# BitBeaconS.net
KiCad netlist of a schematic drawn in EAGLE
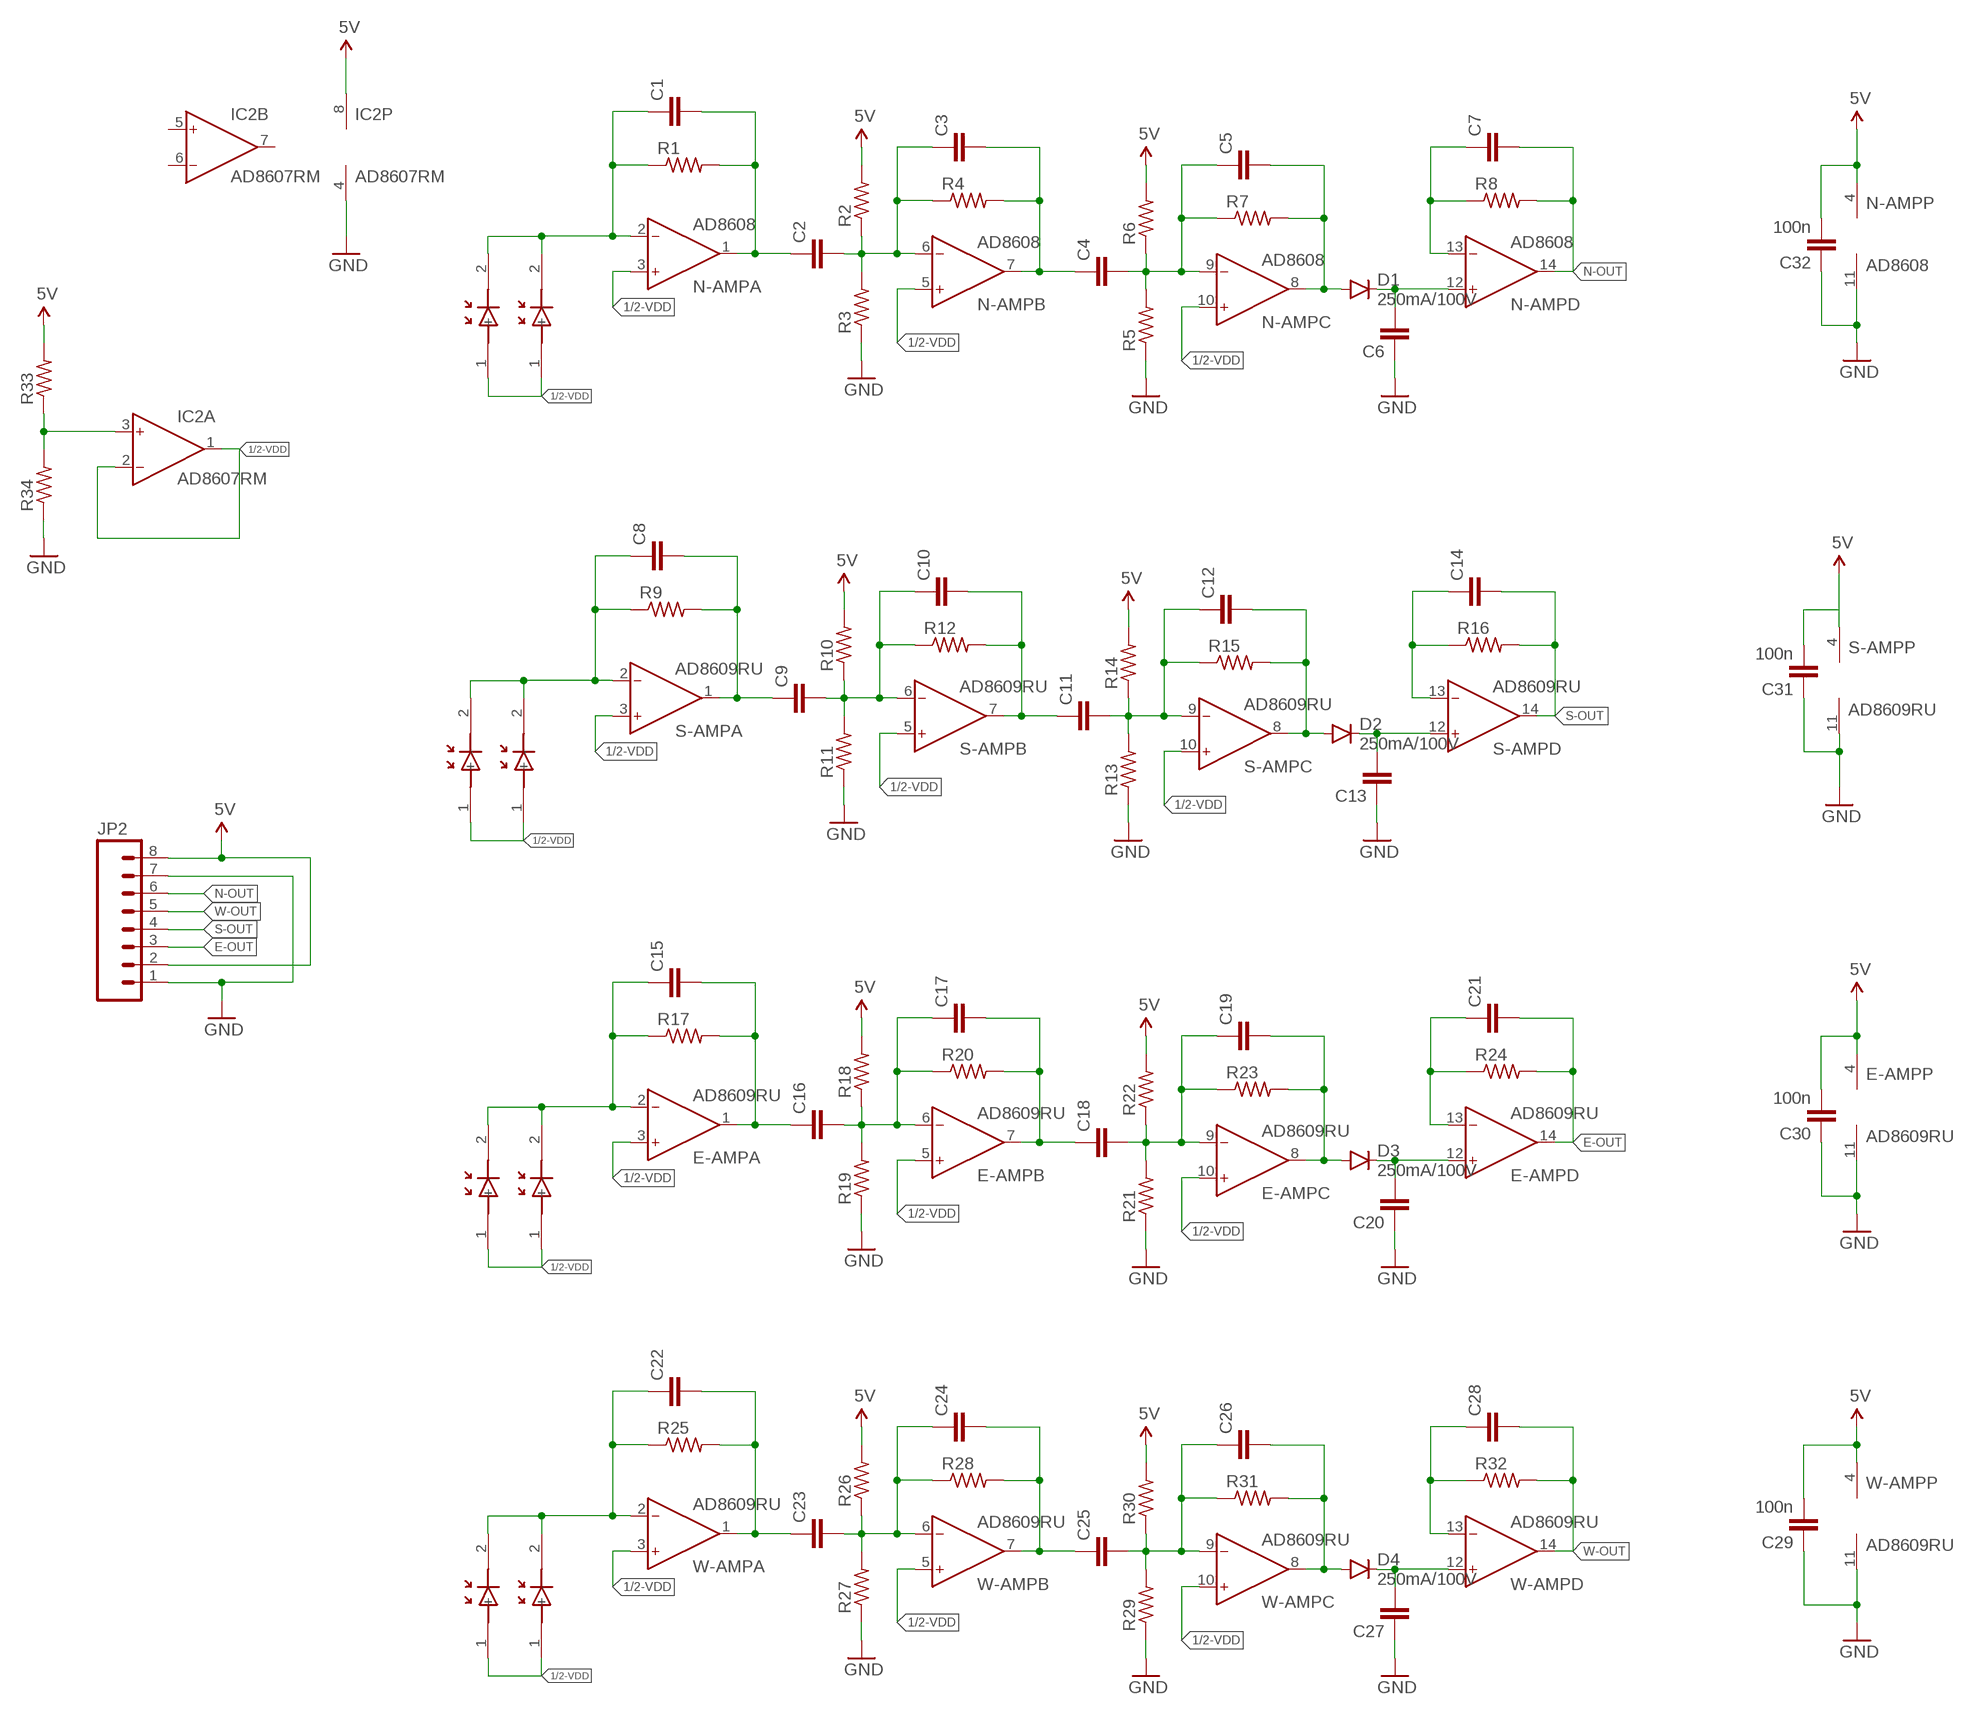
[diagram p0: schematic, sheet 1]

(export (version "E")
  (design (tool "Eeschema 10.0.6"))
  (components
    (comp (ref "C1")
      (value "C-EUC0805")
      (footprint "eagle-import:C0805")
      (libsource (lib "eagle-import") (part "C-EUC0805"))
    )
    (comp (ref "C2")
      (value "C-EUC0805")
      (footprint "eagle-import:C0805")
      (libsource (lib "eagle-import") (part "C-EUC0805"))
    )
    (comp (ref "C3")
      (value "C-EUC0805")
      (footprint "eagle-import:C0805")
      (libsource (lib "eagle-import") (part "C-EUC0805"))
    )
    (comp (ref "C4")
      (value "C-EUC0805")
      (footprint "eagle-import:C0805")
      (libsource (lib "eagle-import") (part "C-EUC0805"))
    )
    (comp (ref "C5")
      (value "C-EUC0805")
      (footprint "eagle-import:C0805")
      (libsource (lib "eagle-import") (part "C-EUC0805"))
    )
    (comp (ref "C6")
      (value "C-EUC0805")
      (footprint "eagle-import:C0805")
      (libsource (lib "eagle-import") (part "C-EUC0805"))
    )
    (comp (ref "C7")
      (value "C-EUC0805")
      (footprint "eagle-import:C0805")
      (libsource (lib "eagle-import") (part "C-EUC0805"))
    )
    (comp (ref "C8")
      (value "C-EUC0805")
      (footprint "eagle-import:C0805")
      (libsource (lib "eagle-import") (part "C-EUC0805"))
    )
    (comp (ref "C9")
      (value "C-EUC0805")
      (footprint "eagle-import:C0805")
      (libsource (lib "eagle-import") (part "C-EUC0805"))
    )
    (comp (ref "C10")
      (value "C-EUC0805")
      (footprint "eagle-import:C0805")
      (libsource (lib "eagle-import") (part "C-EUC0805"))
    )
    (comp (ref "C11")
      (value "C-EUC0805")
      (footprint "eagle-import:C0805")
      (libsource (lib "eagle-import") (part "C-EUC0805"))
    )
    (comp (ref "C12")
      (value "C-EUC0805")
      (footprint "eagle-import:C0805")
      (libsource (lib "eagle-import") (part "C-EUC0805"))
    )
    (comp (ref "C13")
      (value "C-EUC0805")
      (footprint "eagle-import:C0805")
      (libsource (lib "eagle-import") (part "C-EUC0805"))
    )
    (comp (ref "C14")
      (value "C-EUC0805")
      (footprint "eagle-import:C0805")
      (libsource (lib "eagle-import") (part "C-EUC0805"))
    )
    (comp (ref "C15")
      (value "C-EUC0805")
      (footprint "eagle-import:C0805")
      (libsource (lib "eagle-import") (part "C-EUC0805"))
    )
    (comp (ref "C16")
      (value "C-EUC0805")
      (footprint "eagle-import:C0805")
      (libsource (lib "eagle-import") (part "C-EUC0805"))
    )
    (comp (ref "C17")
      (value "C-EUC0805")
      (footprint "eagle-import:C0805")
      (libsource (lib "eagle-import") (part "C-EUC0805"))
    )
    (comp (ref "C18")
      (value "C-EUC0805")
      (footprint "eagle-import:C0805")
      (libsource (lib "eagle-import") (part "C-EUC0805"))
    )
    (comp (ref "C19")
      (value "C-EUC0805")
      (footprint "eagle-import:C0805")
      (libsource (lib "eagle-import") (part "C-EUC0805"))
    )
    (comp (ref "C20")
      (value "C-EUC0805")
      (footprint "eagle-import:C0805")
      (libsource (lib "eagle-import") (part "C-EUC0805"))
    )
    (comp (ref "C21")
      (value "C-EUC0805")
      (footprint "eagle-import:C0805")
      (libsource (lib "eagle-import") (part "C-EUC0805"))
    )
    (comp (ref "C22")
      (value "C-EUC0805")
      (footprint "eagle-import:C0805")
      (libsource (lib "eagle-import") (part "C-EUC0805"))
    )
    (comp (ref "C23")
      (value "C-EUC0805")
      (footprint "eagle-import:C0805")
      (libsource (lib "eagle-import") (part "C-EUC0805"))
    )
    (comp (ref "C24")
      (value "C-EUC0805")
      (footprint "eagle-import:C0805")
      (libsource (lib "eagle-import") (part "C-EUC0805"))
    )
    (comp (ref "C25")
      (value "C-EUC0805")
      (footprint "eagle-import:C0805")
      (libsource (lib "eagle-import") (part "C-EUC0805"))
    )
    (comp (ref "C26")
      (value "C-EUC0805")
      (footprint "eagle-import:C0805")
      (libsource (lib "eagle-import") (part "C-EUC0805"))
    )
    (comp (ref "C27")
      (value "C-EUC0805")
      (footprint "eagle-import:C0805")
      (libsource (lib "eagle-import") (part "C-EUC0805"))
    )
    (comp (ref "C28")
      (value "C-EUC0805")
      (footprint "eagle-import:C0805")
      (libsource (lib "eagle-import") (part "C-EUC0805"))
    )
    (comp (ref "C29")
      (value "100n")
      (footprint "eagle-import:C0805")
      (libsource (lib "eagle-import") (part "C-EUC0805"))
    )
    (comp (ref "C30")
      (value "100n")
      (footprint "eagle-import:C0805")
      (libsource (lib "eagle-import") (part "C-EUC0805"))
    )
    (comp (ref "C31")
      (value "100n")
      (footprint "eagle-import:C0805")
      (libsource (lib "eagle-import") (part "C-EUC0805"))
    )
    (comp (ref "C32")
      (value "100n")
      (footprint "eagle-import:C0805")
      (libsource (lib "eagle-import") (part "C-EUC0805"))
    )
    (comp (ref "D1")
      (value "250mA/100V")
      (footprint "eagle-import:SOD-323")
      (libsource (lib "eagle-import") (part "DIODEBAS16"))
    )
    (comp (ref "D2")
      (value "250mA/100V")
      (footprint "eagle-import:SOD-323")
      (libsource (lib "eagle-import") (part "DIODEBAS16"))
    )
    (comp (ref "D3")
      (value "250mA/100V")
      (footprint "eagle-import:SOD-323")
      (libsource (lib "eagle-import") (part "DIODEBAS16"))
    )
    (comp (ref "D4")
      (value "250mA/100V")
      (footprint "eagle-import:SOD-323")
      (libsource (lib "eagle-import") (part "DIODEBAS16"))
    )
    (comp (ref "E-AMP")
      (value "AD8609RU")
      (footprint "eagle-import:TSSOP14")
      (fields (field (name "MF") "ALTERA CORPORATION") (field (name "MPN") "AD8609ARUZ"))
      (libsource (lib "eagle-import") (part "AD8609RU"))
    )
    (comp (ref "E-PD")
      (value "BPW46")
      (footprint "eagle-import:PIN-PHOTODIODE")
      (libsource (lib "eagle-import") (part "BPW46"))
    )
    (comp (ref "E-PD1")
      (value "BPW46")
      (footprint "eagle-import:PIN-PHOTODIODE")
      (libsource (lib "eagle-import") (part "BPW46"))
    )
    (comp (ref "IC2")
      (value "AD8607RM")
      (footprint "eagle-import:MSOP08")
      (fields (field (name "MF") "ALTERA CORPORATION") (field (name "MPN") "AD8607ARMZ-REEL"))
      (libsource (lib "eagle-import") (part "AD8607RM"))
    )
    (comp (ref "JP2")
      (value "M08NO_SILK")
      (footprint "eagle-import:1X08_PIN1_NO_SILK")
      (libsource (lib "eagle-import") (part "M08NO_SILK"))
    )
    (comp (ref "N-AMP")
      (value "AD8608")
      (footprint "eagle-import:TSSOP14")
      (fields (field (name "MF") "ALTERA CORPORATION") (field (name "MPN") "AD8609ARUZ"))
      (libsource (lib "eagle-import") (part "AD8609RU"))
    )
    (comp (ref "N-PD")
      (value "BPW46")
      (footprint "eagle-import:PIN-PHOTODIODE")
      (libsource (lib "eagle-import") (part "BPW46"))
    )
    (comp (ref "N-PD1")
      (value "BPW46")
      (footprint "eagle-import:PIN-PHOTODIODE")
      (libsource (lib "eagle-import") (part "BPW46"))
    )
    (comp (ref "R1")
      (value "R-US_R0805")
      (footprint "eagle-import:R0805")
      (libsource (lib "eagle-import") (part "R-US_R0805"))
    )
    (comp (ref "R2")
      (value "R-US_R0805")
      (footprint "eagle-import:R0805")
      (libsource (lib "eagle-import") (part "R-US_R0805"))
    )
    (comp (ref "R3")
      (value "R-US_R0805")
      (footprint "eagle-import:R0805")
      (libsource (lib "eagle-import") (part "R-US_R0805"))
    )
    (comp (ref "R4")
      (value "R-US_R0805")
      (footprint "eagle-import:R0805")
      (libsource (lib "eagle-import") (part "R-US_R0805"))
    )
    (comp (ref "R5")
      (value "R-US_R0805")
      (footprint "eagle-import:R0805")
      (libsource (lib "eagle-import") (part "R-US_R0805"))
    )
    (comp (ref "R6")
      (value "R-US_R0805")
      (footprint "eagle-import:R0805")
      (libsource (lib "eagle-import") (part "R-US_R0805"))
    )
    (comp (ref "R7")
      (value "R-US_R0805")
      (footprint "eagle-import:R0805")
      (libsource (lib "eagle-import") (part "R-US_R0805"))
    )
    (comp (ref "R8")
      (value "R-US_R0805")
      (footprint "eagle-import:R0805")
      (libsource (lib "eagle-import") (part "R-US_R0805"))
    )
    (comp (ref "R9")
      (value "R-US_R0805")
      (footprint "eagle-import:R0805")
      (libsource (lib "eagle-import") (part "R-US_R0805"))
    )
    (comp (ref "R10")
      (value "R-US_R0805")
      (footprint "eagle-import:R0805")
      (libsource (lib "eagle-import") (part "R-US_R0805"))
    )
    (comp (ref "R11")
      (value "R-US_R0805")
      (footprint "eagle-import:R0805")
      (libsource (lib "eagle-import") (part "R-US_R0805"))
    )
    (comp (ref "R12")
      (value "R-US_R0805")
      (footprint "eagle-import:R0805")
      (libsource (lib "eagle-import") (part "R-US_R0805"))
    )
    (comp (ref "R13")
      (value "R-US_R0805")
      (footprint "eagle-import:R0805")
      (libsource (lib "eagle-import") (part "R-US_R0805"))
    )
    (comp (ref "R14")
      (value "R-US_R0805")
      (footprint "eagle-import:R0805")
      (libsource (lib "eagle-import") (part "R-US_R0805"))
    )
    (comp (ref "R15")
      (value "R-US_R0805")
      (footprint "eagle-import:R0805")
      (libsource (lib "eagle-import") (part "R-US_R0805"))
    )
    (comp (ref "R16")
      (value "R-US_R0805")
      (footprint "eagle-import:R0805")
      (libsource (lib "eagle-import") (part "R-US_R0805"))
    )
    (comp (ref "R17")
      (value "R-US_R0805")
      (footprint "eagle-import:R0805")
      (libsource (lib "eagle-import") (part "R-US_R0805"))
    )
    (comp (ref "R18")
      (value "R-US_R0805")
      (footprint "eagle-import:R0805")
      (libsource (lib "eagle-import") (part "R-US_R0805"))
    )
    (comp (ref "R19")
      (value "R-US_R0805")
      (footprint "eagle-import:R0805")
      (libsource (lib "eagle-import") (part "R-US_R0805"))
    )
    (comp (ref "R20")
      (value "R-US_R0805")
      (footprint "eagle-import:R0805")
      (libsource (lib "eagle-import") (part "R-US_R0805"))
    )
    (comp (ref "R21")
      (value "R-US_R0805")
      (footprint "eagle-import:R0805")
      (libsource (lib "eagle-import") (part "R-US_R0805"))
    )
    (comp (ref "R22")
      (value "R-US_R0805")
      (footprint "eagle-import:R0805")
      (libsource (lib "eagle-import") (part "R-US_R0805"))
    )
    (comp (ref "R23")
      (value "R-US_R0805")
      (footprint "eagle-import:R0805")
      (libsource (lib "eagle-import") (part "R-US_R0805"))
    )
    (comp (ref "R24")
      (value "R-US_R0805")
      (footprint "eagle-import:R0805")
      (libsource (lib "eagle-import") (part "R-US_R0805"))
    )
    (comp (ref "R25")
      (value "R-US_R0805")
      (footprint "eagle-import:R0805")
      (libsource (lib "eagle-import") (part "R-US_R0805"))
    )
    (comp (ref "R26")
      (value "R-US_R0805")
      (footprint "eagle-import:R0805")
      (libsource (lib "eagle-import") (part "R-US_R0805"))
    )
    (comp (ref "R27")
      (value "R-US_R0805")
      (footprint "eagle-import:R0805")
      (libsource (lib "eagle-import") (part "R-US_R0805"))
    )
    (comp (ref "R28")
      (value "R-US_R0805")
      (footprint "eagle-import:R0805")
      (libsource (lib "eagle-import") (part "R-US_R0805"))
    )
    (comp (ref "R29")
      (value "R-US_R0805")
      (footprint "eagle-import:R0805")
      (libsource (lib "eagle-import") (part "R-US_R0805"))
    )
    (comp (ref "R30")
      (value "R-US_R0805")
      (footprint "eagle-import:R0805")
      (libsource (lib "eagle-import") (part "R-US_R0805"))
    )
    (comp (ref "R31")
      (value "R-US_R0805")
      (footprint "eagle-import:R0805")
      (libsource (lib "eagle-import") (part "R-US_R0805"))
    )
    (comp (ref "R32")
      (value "R-US_R0805")
      (footprint "eagle-import:R0805")
      (libsource (lib "eagle-import") (part "R-US_R0805"))
    )
    (comp (ref "R33")
      (value "R-US_R0805")
      (footprint "eagle-import:R0805")
      (libsource (lib "eagle-import") (part "R-US_R0805"))
    )
    (comp (ref "R34")
      (value "R-US_R0805")
      (footprint "eagle-import:R0805")
      (libsource (lib "eagle-import") (part "R-US_R0805"))
    )
    (comp (ref "S-AMP")
      (value "AD8609RU")
      (footprint "eagle-import:TSSOP14")
      (fields (field (name "MF") "ALTERA CORPORATION") (field (name "MPN") "AD8609ARUZ"))
      (libsource (lib "eagle-import") (part "AD8609RU"))
    )
    (comp (ref "S-PD")
      (value "BPW46")
      (footprint "eagle-import:PIN-PHOTODIODE")
      (libsource (lib "eagle-import") (part "BPW46"))
    )
    (comp (ref "S-PD1")
      (value "BPW46")
      (footprint "eagle-import:PIN-PHOTODIODE")
      (libsource (lib "eagle-import") (part "BPW46"))
    )
    (comp (ref "W-AMP")
      (value "AD8609RU")
      (footprint "eagle-import:TSSOP14")
      (fields (field (name "MF") "ALTERA CORPORATION") (field (name "MPN") "AD8609ARUZ"))
      (libsource (lib "eagle-import") (part "AD8609RU"))
    )
    (comp (ref "W-PD")
      (value "BPW46")
      (footprint "eagle-import:PIN-PHOTODIODE")
      (libsource (lib "eagle-import") (part "BPW46"))
    )
    (comp (ref "W-PD1")
      (value "BPW46")
      (footprint "eagle-import:PIN-PHOTODIODE")
      (libsource (lib "eagle-import") (part "BPW46"))
    )
  )
  (nets
    (net (code "1") (name "1{slash}2-VDD") (class "Default")
      (node (ref "E-AMP") (pin "10") (pinfunction "IN+_10") (pintype "input"))
      (node (ref "E-AMP") (pin "3") (pinfunction "IN+_3") (pintype "input"))
      (node (ref "E-AMP") (pin "5") (pinfunction "IN+_5") (pintype "input"))
      (node (ref "E-PD") (pin "1") (pinfunction "+_1") (pintype "bidirectional"))
      (node (ref "E-PD1") (pin "1") (pinfunction "+_1") (pintype "bidirectional"))
      (node (ref "IC2") (pin "1") (pinfunction "OUT_1") (pintype "output"))
      (node (ref "IC2") (pin "2") (pinfunction "IN-_2") (pintype "input"))
      (node (ref "N-AMP") (pin "10") (pinfunction "IN+_10") (pintype "input"))
      (node (ref "N-AMP") (pin "3") (pinfunction "IN+_3") (pintype "input"))
      (node (ref "N-AMP") (pin "5") (pinfunction "IN+_5") (pintype "input"))
      (node (ref "N-PD") (pin "1") (pinfunction "+_1") (pintype "bidirectional"))
      (node (ref "N-PD1") (pin "1") (pinfunction "+_1") (pintype "bidirectional"))
      (node (ref "S-AMP") (pin "10") (pinfunction "IN+_10") (pintype "input"))
      (node (ref "S-AMP") (pin "3") (pinfunction "IN+_3") (pintype "input"))
      (node (ref "S-AMP") (pin "5") (pinfunction "IN+_5") (pintype "input"))
      (node (ref "S-PD") (pin "1") (pinfunction "+_1") (pintype "bidirectional"))
      (node (ref "S-PD1") (pin "1") (pinfunction "+_1") (pintype "bidirectional"))
      (node (ref "W-AMP") (pin "10") (pinfunction "IN+_10") (pintype "input"))
      (node (ref "W-AMP") (pin "3") (pinfunction "IN+_3") (pintype "input"))
      (node (ref "W-AMP") (pin "5") (pinfunction "IN+_5") (pintype "input"))
      (node (ref "W-PD") (pin "1") (pinfunction "+_1") (pintype "bidirectional"))
      (node (ref "W-PD1") (pin "1") (pinfunction "+_1") (pintype "bidirectional"))
    )
    (net (code "2") (name "5V") (class "Default")
      (node (ref "C29") (pin "2") (pinfunction "2_2") (pintype "passive"))
      (node (ref "C30") (pin "2") (pinfunction "2_2") (pintype "passive"))
      (node (ref "C31") (pin "2") (pinfunction "2_2") (pintype "passive"))
      (node (ref "C32") (pin "2") (pinfunction "2_2") (pintype "passive"))
      (node (ref "E-AMP") (pin "4") (pinfunction "V+_4") (pintype "power_in"))
      (node (ref "IC2") (pin "8") (pinfunction "V+_8") (pintype "power_in"))
      (node (ref "JP2") (pin "2") (pinfunction "2_2") (pintype "passive"))
      (node (ref "JP2") (pin "8") (pinfunction "8_8") (pintype "passive"))
      (node (ref "N-AMP") (pin "4") (pinfunction "V+_4") (pintype "power_in"))
      (node (ref "R10") (pin "2") (pinfunction "2_2") (pintype "passive"))
      (node (ref "R14") (pin "2") (pinfunction "2_2") (pintype "passive"))
      (node (ref "R18") (pin "2") (pinfunction "2_2") (pintype "passive"))
      (node (ref "R2") (pin "2") (pinfunction "2_2") (pintype "passive"))
      (node (ref "R22") (pin "2") (pinfunction "2_2") (pintype "passive"))
      (node (ref "R26") (pin "2") (pinfunction "2_2") (pintype "passive"))
      (node (ref "R30") (pin "2") (pinfunction "2_2") (pintype "passive"))
      (node (ref "R33") (pin "2") (pinfunction "2_2") (pintype "passive"))
      (node (ref "R6") (pin "2") (pinfunction "2_2") (pintype "passive"))
      (node (ref "S-AMP") (pin "4") (pinfunction "V+_4") (pintype "power_in"))
      (node (ref "W-AMP") (pin "4") (pinfunction "V+_4") (pintype "power_in"))
    )
    (net (code "3") (name "E-OUT") (class "Default")
      (node (ref "C21") (pin "2") (pinfunction "2_2") (pintype "passive"))
      (node (ref "E-AMP") (pin "14") (pinfunction "OUT_14") (pintype "output"))
      (node (ref "JP2") (pin "3") (pinfunction "3_3") (pintype "passive"))
      (node (ref "R24") (pin "2") (pinfunction "2_2") (pintype "passive"))
    )
    (net (code "4") (name "GND") (class "Default")
      (node (ref "C13") (pin "1") (pinfunction "1_1") (pintype "passive"))
      (node (ref "C20") (pin "1") (pinfunction "1_1") (pintype "passive"))
      (node (ref "C27") (pin "1") (pinfunction "1_1") (pintype "passive"))
      (node (ref "C29") (pin "1") (pinfunction "1_1") (pintype "passive"))
      (node (ref "C30") (pin "1") (pinfunction "1_1") (pintype "passive"))
      (node (ref "C31") (pin "1") (pinfunction "1_1") (pintype "passive"))
      (node (ref "C32") (pin "1") (pinfunction "1_1") (pintype "passive"))
      (node (ref "C6") (pin "1") (pinfunction "1_1") (pintype "passive"))
      (node (ref "E-AMP") (pin "11") (pinfunction "V-_11") (pintype "power_in"))
      (node (ref "IC2") (pin "4") (pinfunction "V-_4") (pintype "power_in"))
      (node (ref "JP2") (pin "1") (pinfunction "1_1") (pintype "passive"))
      (node (ref "JP2") (pin "7") (pinfunction "7_7") (pintype "passive"))
      (node (ref "N-AMP") (pin "11") (pinfunction "V-_11") (pintype "power_in"))
      (node (ref "R11") (pin "1") (pinfunction "1_1") (pintype "passive"))
      (node (ref "R13") (pin "1") (pinfunction "1_1") (pintype "passive"))
      (node (ref "R19") (pin "1") (pinfunction "1_1") (pintype "passive"))
      (node (ref "R21") (pin "1") (pinfunction "1_1") (pintype "passive"))
      (node (ref "R27") (pin "1") (pinfunction "1_1") (pintype "passive"))
      (node (ref "R29") (pin "1") (pinfunction "1_1") (pintype "passive"))
      (node (ref "R3") (pin "1") (pinfunction "1_1") (pintype "passive"))
      (node (ref "R34") (pin "1") (pinfunction "1_1") (pintype "passive"))
      (node (ref "R5") (pin "1") (pinfunction "1_1") (pintype "passive"))
      (node (ref "S-AMP") (pin "11") (pinfunction "V-_11") (pintype "power_in"))
      (node (ref "W-AMP") (pin "11") (pinfunction "V-_11") (pintype "power_in"))
    )
    (net (code "5") (name "N-OUT") (class "Default")
      (node (ref "C7") (pin "2") (pinfunction "2_2") (pintype "passive"))
      (node (ref "JP2") (pin "6") (pinfunction "6_6") (pintype "passive"))
      (node (ref "N-AMP") (pin "14") (pinfunction "OUT_14") (pintype "output"))
      (node (ref "R8") (pin "2") (pinfunction "2_2") (pintype "passive"))
    )
    (net (code "6") (name "Net-(E-AMPA-IN-)") (class "Default")
      (node (ref "C15") (pin "1") (pinfunction "1_1") (pintype "passive"))
      (node (ref "E-AMP") (pin "2") (pinfunction "IN-_2") (pintype "input"))
      (node (ref "E-PD") (pin "2") (pinfunction "-_2") (pintype "bidirectional"))
      (node (ref "E-PD1") (pin "2") (pinfunction "-_2") (pintype "bidirectional"))
      (node (ref "R17") (pin "1") (pinfunction "1_1") (pintype "passive"))
    )
    (net (code "7") (name "Net-(E-AMPA-OUT)") (class "Default")
      (node (ref "C15") (pin "2") (pinfunction "2_2") (pintype "passive"))
      (node (ref "C16") (pin "1") (pinfunction "1_1") (pintype "passive"))
      (node (ref "E-AMP") (pin "1") (pinfunction "OUT_1") (pintype "output"))
      (node (ref "R17") (pin "2") (pinfunction "2_2") (pintype "passive"))
    )
    (net (code "8") (name "Net-(E-AMPB-IN-)") (class "Default")
      (node (ref "C16") (pin "2") (pinfunction "2_2") (pintype "passive"))
      (node (ref "C17") (pin "1") (pinfunction "1_1") (pintype "passive"))
      (node (ref "E-AMP") (pin "6") (pinfunction "IN-_6") (pintype "input"))
      (node (ref "R18") (pin "1") (pinfunction "1_1") (pintype "passive"))
      (node (ref "R19") (pin "2") (pinfunction "2_2") (pintype "passive"))
      (node (ref "R20") (pin "1") (pinfunction "1_1") (pintype "passive"))
    )
    (net (code "9") (name "Net-(E-AMPB-OUT)") (class "Default")
      (node (ref "C17") (pin "2") (pinfunction "2_2") (pintype "passive"))
      (node (ref "C18") (pin "1") (pinfunction "1_1") (pintype "passive"))
      (node (ref "E-AMP") (pin "7") (pinfunction "OUT_7") (pintype "output"))
      (node (ref "R20") (pin "2") (pinfunction "2_2") (pintype "passive"))
    )
    (net (code "10") (name "Net-(E-AMPC-IN-)") (class "Default")
      (node (ref "C18") (pin "2") (pinfunction "2_2") (pintype "passive"))
      (node (ref "C19") (pin "1") (pinfunction "1_1") (pintype "passive"))
      (node (ref "E-AMP") (pin "9") (pinfunction "IN-_9") (pintype "input"))
      (node (ref "R21") (pin "2") (pinfunction "2_2") (pintype "passive"))
      (node (ref "R22") (pin "1") (pinfunction "1_1") (pintype "passive"))
      (node (ref "R23") (pin "1") (pinfunction "1_1") (pintype "passive"))
    )
    (net (code "11") (name "Net-(E-AMPC-OUT)") (class "Default")
      (node (ref "C19") (pin "2") (pinfunction "2_2") (pintype "passive"))
      (node (ref "D3") (pin "A") (pinfunction "A_A") (pintype "passive"))
      (node (ref "E-AMP") (pin "8") (pinfunction "OUT_8") (pintype "output"))
      (node (ref "R23") (pin "2") (pinfunction "2_2") (pintype "passive"))
    )
    (net (code "12") (name "Net-(E-AMPD-IN+)") (class "Default")
      (node (ref "C20") (pin "2") (pinfunction "2_2") (pintype "passive"))
      (node (ref "D3") (pin "C") (pinfunction "C_C") (pintype "passive"))
      (node (ref "E-AMP") (pin "12") (pinfunction "IN+_12") (pintype "input"))
    )
    (net (code "13") (name "Net-(E-AMPD-IN-)") (class "Default")
      (node (ref "C21") (pin "1") (pinfunction "1_1") (pintype "passive"))
      (node (ref "E-AMP") (pin "13") (pinfunction "IN-_13") (pintype "input"))
      (node (ref "R24") (pin "1") (pinfunction "1_1") (pintype "passive"))
    )
    (net (code "14") (name "Net-(IC2A-IN+)") (class "Default")
      (node (ref "IC2") (pin "3") (pinfunction "IN+_3") (pintype "input"))
      (node (ref "R33") (pin "1") (pinfunction "1_1") (pintype "passive"))
      (node (ref "R34") (pin "2") (pinfunction "2_2") (pintype "passive"))
    )
    (net (code "15") (name "Net-(N-AMPA-IN-)") (class "Default")
      (node (ref "C1") (pin "1") (pinfunction "1_1") (pintype "passive"))
      (node (ref "N-AMP") (pin "2") (pinfunction "IN-_2") (pintype "input"))
      (node (ref "N-PD") (pin "2") (pinfunction "-_2") (pintype "bidirectional"))
      (node (ref "N-PD1") (pin "2") (pinfunction "-_2") (pintype "bidirectional"))
      (node (ref "R1") (pin "1") (pinfunction "1_1") (pintype "passive"))
    )
    (net (code "16") (name "Net-(N-AMPA-OUT)") (class "Default")
      (node (ref "C1") (pin "2") (pinfunction "2_2") (pintype "passive"))
      (node (ref "C2") (pin "1") (pinfunction "1_1") (pintype "passive"))
      (node (ref "N-AMP") (pin "1") (pinfunction "OUT_1") (pintype "output"))
      (node (ref "R1") (pin "2") (pinfunction "2_2") (pintype "passive"))
    )
    (net (code "17") (name "Net-(N-AMPB-IN-)") (class "Default")
      (node (ref "C2") (pin "2") (pinfunction "2_2") (pintype "passive"))
      (node (ref "C3") (pin "1") (pinfunction "1_1") (pintype "passive"))
      (node (ref "N-AMP") (pin "6") (pinfunction "IN-_6") (pintype "input"))
      (node (ref "R2") (pin "1") (pinfunction "1_1") (pintype "passive"))
      (node (ref "R3") (pin "2") (pinfunction "2_2") (pintype "passive"))
      (node (ref "R4") (pin "1") (pinfunction "1_1") (pintype "passive"))
    )
    (net (code "18") (name "Net-(N-AMPB-OUT)") (class "Default")
      (node (ref "C3") (pin "2") (pinfunction "2_2") (pintype "passive"))
      (node (ref "C4") (pin "1") (pinfunction "1_1") (pintype "passive"))
      (node (ref "N-AMP") (pin "7") (pinfunction "OUT_7") (pintype "output"))
      (node (ref "R4") (pin "2") (pinfunction "2_2") (pintype "passive"))
    )
    (net (code "19") (name "Net-(N-AMPC-IN-)") (class "Default")
      (node (ref "C4") (pin "2") (pinfunction "2_2") (pintype "passive"))
      (node (ref "C5") (pin "1") (pinfunction "1_1") (pintype "passive"))
      (node (ref "N-AMP") (pin "9") (pinfunction "IN-_9") (pintype "input"))
      (node (ref "R5") (pin "2") (pinfunction "2_2") (pintype "passive"))
      (node (ref "R6") (pin "1") (pinfunction "1_1") (pintype "passive"))
      (node (ref "R7") (pin "1") (pinfunction "1_1") (pintype "passive"))
    )
    (net (code "20") (name "Net-(N-AMPC-OUT)") (class "Default")
      (node (ref "C5") (pin "2") (pinfunction "2_2") (pintype "passive"))
      (node (ref "D1") (pin "A") (pinfunction "A_A") (pintype "passive"))
      (node (ref "N-AMP") (pin "8") (pinfunction "OUT_8") (pintype "output"))
      (node (ref "R7") (pin "2") (pinfunction "2_2") (pintype "passive"))
    )
    (net (code "21") (name "Net-(N-AMPD-IN+)") (class "Default")
      (node (ref "C6") (pin "2") (pinfunction "2_2") (pintype "passive"))
      (node (ref "D1") (pin "C") (pinfunction "C_C") (pintype "passive"))
      (node (ref "N-AMP") (pin "12") (pinfunction "IN+_12") (pintype "input"))
    )
    (net (code "22") (name "Net-(N-AMPD-IN-)") (class "Default")
      (node (ref "C7") (pin "1") (pinfunction "1_1") (pintype "passive"))
      (node (ref "N-AMP") (pin "13") (pinfunction "IN-_13") (pintype "input"))
      (node (ref "R8") (pin "1") (pinfunction "1_1") (pintype "passive"))
    )
    (net (code "23") (name "Net-(S-AMPA-IN-)") (class "Default")
      (node (ref "C8") (pin "1") (pinfunction "1_1") (pintype "passive"))
      (node (ref "R9") (pin "1") (pinfunction "1_1") (pintype "passive"))
      (node (ref "S-AMP") (pin "2") (pinfunction "IN-_2") (pintype "input"))
      (node (ref "S-PD") (pin "2") (pinfunction "-_2") (pintype "bidirectional"))
      (node (ref "S-PD1") (pin "2") (pinfunction "-_2") (pintype "bidirectional"))
    )
    (net (code "24") (name "Net-(S-AMPA-OUT)") (class "Default")
      (node (ref "C8") (pin "2") (pinfunction "2_2") (pintype "passive"))
      (node (ref "C9") (pin "1") (pinfunction "1_1") (pintype "passive"))
      (node (ref "R9") (pin "2") (pinfunction "2_2") (pintype "passive"))
      (node (ref "S-AMP") (pin "1") (pinfunction "OUT_1") (pintype "output"))
    )
    (net (code "25") (name "Net-(S-AMPB-IN-)") (class "Default")
      (node (ref "C10") (pin "1") (pinfunction "1_1") (pintype "passive"))
      (node (ref "C9") (pin "2") (pinfunction "2_2") (pintype "passive"))
      (node (ref "R10") (pin "1") (pinfunction "1_1") (pintype "passive"))
      (node (ref "R11") (pin "2") (pinfunction "2_2") (pintype "passive"))
      (node (ref "R12") (pin "1") (pinfunction "1_1") (pintype "passive"))
      (node (ref "S-AMP") (pin "6") (pinfunction "IN-_6") (pintype "input"))
    )
    (net (code "26") (name "Net-(S-AMPB-OUT)") (class "Default")
      (node (ref "C10") (pin "2") (pinfunction "2_2") (pintype "passive"))
      (node (ref "C11") (pin "1") (pinfunction "1_1") (pintype "passive"))
      (node (ref "R12") (pin "2") (pinfunction "2_2") (pintype "passive"))
      (node (ref "S-AMP") (pin "7") (pinfunction "OUT_7") (pintype "output"))
    )
    (net (code "27") (name "Net-(S-AMPC-IN-)") (class "Default")
      (node (ref "C11") (pin "2") (pinfunction "2_2") (pintype "passive"))
      (node (ref "C12") (pin "1") (pinfunction "1_1") (pintype "passive"))
      (node (ref "R13") (pin "2") (pinfunction "2_2") (pintype "passive"))
      (node (ref "R14") (pin "1") (pinfunction "1_1") (pintype "passive"))
      (node (ref "R15") (pin "1") (pinfunction "1_1") (pintype "passive"))
      (node (ref "S-AMP") (pin "9") (pinfunction "IN-_9") (pintype "input"))
    )
    (net (code "28") (name "Net-(S-AMPC-OUT)") (class "Default")
      (node (ref "C12") (pin "2") (pinfunction "2_2") (pintype "passive"))
      (node (ref "D2") (pin "A") (pinfunction "A_A") (pintype "passive"))
      (node (ref "R15") (pin "2") (pinfunction "2_2") (pintype "passive"))
      (node (ref "S-AMP") (pin "8") (pinfunction "OUT_8") (pintype "output"))
    )
    (net (code "29") (name "Net-(S-AMPD-IN+)") (class "Default")
      (node (ref "C13") (pin "2") (pinfunction "2_2") (pintype "passive"))
      (node (ref "D2") (pin "C") (pinfunction "C_C") (pintype "passive"))
      (node (ref "S-AMP") (pin "12") (pinfunction "IN+_12") (pintype "input"))
    )
    (net (code "30") (name "Net-(S-AMPD-IN-)") (class "Default")
      (node (ref "C14") (pin "1") (pinfunction "1_1") (pintype "passive"))
      (node (ref "R16") (pin "1") (pinfunction "1_1") (pintype "passive"))
      (node (ref "S-AMP") (pin "13") (pinfunction "IN-_13") (pintype "input"))
    )
    (net (code "31") (name "Net-(W-AMPA-IN-)") (class "Default")
      (node (ref "C22") (pin "1") (pinfunction "1_1") (pintype "passive"))
      (node (ref "R25") (pin "1") (pinfunction "1_1") (pintype "passive"))
      (node (ref "W-AMP") (pin "2") (pinfunction "IN-_2") (pintype "input"))
      (node (ref "W-PD") (pin "2") (pinfunction "-_2") (pintype "bidirectional"))
      (node (ref "W-PD1") (pin "2") (pinfunction "-_2") (pintype "bidirectional"))
    )
    (net (code "32") (name "Net-(W-AMPA-OUT)") (class "Default")
      (node (ref "C22") (pin "2") (pinfunction "2_2") (pintype "passive"))
      (node (ref "C23") (pin "1") (pinfunction "1_1") (pintype "passive"))
      (node (ref "R25") (pin "2") (pinfunction "2_2") (pintype "passive"))
      (node (ref "W-AMP") (pin "1") (pinfunction "OUT_1") (pintype "output"))
    )
    (net (code "33") (name "Net-(W-AMPB-IN-)") (class "Default")
      (node (ref "C23") (pin "2") (pinfunction "2_2") (pintype "passive"))
      (node (ref "C24") (pin "1") (pinfunction "1_1") (pintype "passive"))
      (node (ref "R26") (pin "1") (pinfunction "1_1") (pintype "passive"))
      (node (ref "R27") (pin "2") (pinfunction "2_2") (pintype "passive"))
      (node (ref "R28") (pin "1") (pinfunction "1_1") (pintype "passive"))
      (node (ref "W-AMP") (pin "6") (pinfunction "IN-_6") (pintype "input"))
    )
    (net (code "34") (name "Net-(W-AMPB-OUT)") (class "Default")
      (node (ref "C24") (pin "2") (pinfunction "2_2") (pintype "passive"))
      (node (ref "C25") (pin "1") (pinfunction "1_1") (pintype "passive"))
      (node (ref "R28") (pin "2") (pinfunction "2_2") (pintype "passive"))
      (node (ref "W-AMP") (pin "7") (pinfunction "OUT_7") (pintype "output"))
    )
    (net (code "35") (name "Net-(W-AMPC-IN-)") (class "Default")
      (node (ref "C25") (pin "2") (pinfunction "2_2") (pintype "passive"))
      (node (ref "C26") (pin "1") (pinfunction "1_1") (pintype "passive"))
      (node (ref "R29") (pin "2") (pinfunction "2_2") (pintype "passive"))
      (node (ref "R30") (pin "1") (pinfunction "1_1") (pintype "passive"))
      (node (ref "R31") (pin "1") (pinfunction "1_1") (pintype "passive"))
      (node (ref "W-AMP") (pin "9") (pinfunction "IN-_9") (pintype "input"))
    )
    (net (code "36") (name "Net-(W-AMPC-OUT)") (class "Default")
      (node (ref "C26") (pin "2") (pinfunction "2_2") (pintype "passive"))
      (node (ref "D4") (pin "A") (pinfunction "A_A") (pintype "passive"))
      (node (ref "R31") (pin "2") (pinfunction "2_2") (pintype "passive"))
      (node (ref "W-AMP") (pin "8") (pinfunction "OUT_8") (pintype "output"))
    )
    (net (code "37") (name "Net-(W-AMPD-IN+)") (class "Default")
      (node (ref "C27") (pin "2") (pinfunction "2_2") (pintype "passive"))
      (node (ref "D4") (pin "C") (pinfunction "C_C") (pintype "passive"))
      (node (ref "W-AMP") (pin "12") (pinfunction "IN+_12") (pintype "input"))
    )
    (net (code "38") (name "Net-(W-AMPD-IN-)") (class "Default")
      (node (ref "C28") (pin "1") (pinfunction "1_1") (pintype "passive"))
      (node (ref "R32") (pin "1") (pinfunction "1_1") (pintype "passive"))
      (node (ref "W-AMP") (pin "13") (pinfunction "IN-_13") (pintype "input"))
    )
    (net (code "39") (name "S-OUT") (class "Default")
      (node (ref "C14") (pin "2") (pinfunction "2_2") (pintype "passive"))
      (node (ref "JP2") (pin "4") (pinfunction "4_4") (pintype "passive"))
      (node (ref "R16") (pin "2") (pinfunction "2_2") (pintype "passive"))
      (node (ref "S-AMP") (pin "14") (pinfunction "OUT_14") (pintype "output"))
    )
    (net (code "40") (name "W-OUT") (class "Default")
      (node (ref "C28") (pin "2") (pinfunction "2_2") (pintype "passive"))
      (node (ref "JP2") (pin "5") (pinfunction "5_5") (pintype "passive"))
      (node (ref "R32") (pin "2") (pinfunction "2_2") (pintype "passive"))
      (node (ref "W-AMP") (pin "14") (pinfunction "OUT_14") (pintype "output"))
    )
    (net (code "41") (name "unconnected-(IC2B-IN+-Pad5)") (class "Default")
      (node (ref "IC2") (pin "5") (pinfunction "IN+_5") (pintype "input"))
    )
    (net (code "42") (name "unconnected-(IC2B-IN--Pad6)") (class "Default")
      (node (ref "IC2") (pin "6") (pinfunction "IN-_6") (pintype "input"))
    )
    (net (code "43") (name "unconnected-(IC2B-OUT-Pad7)") (class "Default")
      (node (ref "IC2") (pin "7") (pinfunction "OUT_7") (pintype "output"))
    )
  )
)
